# SMD_Breakout.net
KiCad netlist of a schematic drawn in EAGLE
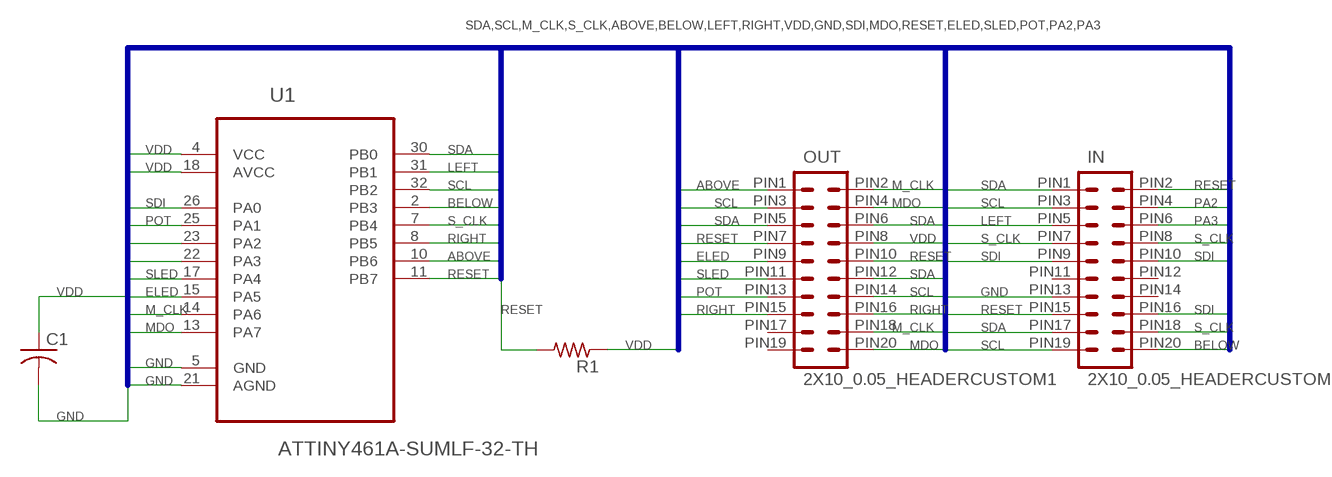
[diagram p0: schematic, sheet 1]

(export (version "E")
  (design (tool "Eeschema 10.0.6"))
  (components
    (comp (ref "C1")
      (value "C-USC0603")
      (footprint "eagle-import:C0603")
      (libsource (lib "eagle-import") (part "C-USC0603"))
    )
    (comp (ref "IN")
      (value "2X10_0.05_HEADERCUSTOM1")
      (footprint "eagle-import:2X10_CUSTOM")
      (libsource (lib "eagle-import") (part "2X10_0.05_HEADERCUSTOM1"))
    )
    (comp (ref "OUT")
      (value "2X10_0.05_HEADERCUSTOM1")
      (footprint "eagle-import:2X10_CUSTOM")
      (libsource (lib "eagle-import") (part "2X10_0.05_HEADERCUSTOM1"))
    )
    (comp (ref "R1")
      (value "R-US_R0603")
      (footprint "eagle-import:R0603")
      (libsource (lib "eagle-import") (part "R-US_R0603"))
    )
    (comp (ref "U1")
      (value "ATTINY461A-SUMLF-32-TH")
      (footprint "eagle-import:MLF32-TH")
      (libsource (lib "eagle-import") (part "ATTINY461A-SUMLF-32-TH"))
    )
  )
  (nets
    (net (code "1") (name "/ABOVE") (class "Default")
      (node (ref "OUT") (pin "PIN1") (pinfunction "1_PIN1") (pintype "passive"))
      (node (ref "U1") (pin "10") (pinfunction "PB6_10") (pintype "bidirectional"))
    )
    (net (code "2") (name "/BELOW") (class "Default")
      (node (ref "IN") (pin "PIN20") (pinfunction "20_PIN20") (pintype "passive"))
      (node (ref "U1") (pin "2") (pinfunction "PB3_2") (pintype "bidirectional"))
    )
    (net (code "3") (name "/ELED") (class "Default")
      (node (ref "OUT") (pin "PIN9") (pinfunction "9_PIN9") (pintype "passive"))
      (node (ref "U1") (pin "15") (pinfunction "PA5_15") (pintype "bidirectional"))
    )
    (net (code "4") (name "/GND") (class "Default")
      (node (ref "C1") (pin "2") (pinfunction "2_2") (pintype "passive"))
      (node (ref "IN") (pin "PIN13") (pinfunction "13_PIN13") (pintype "passive"))
      (node (ref "U1") (pin "21") (pinfunction "AGND_21") (pintype "passive"))
      (node (ref "U1") (pin "5") (pinfunction "GND_5") (pintype "passive"))
    )
    (net (code "5") (name "/LEFT") (class "Default")
      (node (ref "IN") (pin "PIN5") (pinfunction "5_PIN5") (pintype "passive"))
      (node (ref "U1") (pin "31") (pinfunction "PB1_31") (pintype "bidirectional"))
    )
    (net (code "6") (name "/MDO") (class "Default")
      (node (ref "OUT") (pin "PIN20") (pinfunction "20_PIN20") (pintype "passive"))
      (node (ref "OUT") (pin "PIN4") (pinfunction "4_PIN4") (pintype "passive"))
      (node (ref "U1") (pin "13") (pinfunction "PA7_13") (pintype "bidirectional"))
    )
    (net (code "7") (name "/M_CLK") (class "Default")
      (node (ref "OUT") (pin "PIN18") (pinfunction "18_PIN18") (pintype "passive"))
      (node (ref "OUT") (pin "PIN2") (pinfunction "2_PIN2") (pintype "passive"))
      (node (ref "U1") (pin "14") (pinfunction "PA6_14") (pintype "bidirectional"))
    )
    (net (code "8") (name "/PA2") (class "Default")
      (node (ref "IN") (pin "PIN4") (pinfunction "4_PIN4") (pintype "passive"))
      (node (ref "U1") (pin "23") (pinfunction "PA2_23") (pintype "bidirectional"))
    )
    (net (code "9") (name "/PA3") (class "Default")
      (node (ref "IN") (pin "PIN6") (pinfunction "6_PIN6") (pintype "passive"))
      (node (ref "U1") (pin "22") (pinfunction "PA3_22") (pintype "bidirectional"))
    )
    (net (code "10") (name "/POT") (class "Default")
      (node (ref "OUT") (pin "PIN13") (pinfunction "13_PIN13") (pintype "passive"))
      (node (ref "U1") (pin "25") (pinfunction "PA1_25") (pintype "bidirectional"))
    )
    (net (code "11") (name "/RESET") (class "Default")
      (node (ref "IN") (pin "PIN15") (pinfunction "15_PIN15") (pintype "passive"))
      (node (ref "IN") (pin "PIN2") (pinfunction "2_PIN2") (pintype "passive"))
      (node (ref "OUT") (pin "PIN10") (pinfunction "10_PIN10") (pintype "passive"))
      (node (ref "OUT") (pin "PIN7") (pinfunction "7_PIN7") (pintype "passive"))
      (node (ref "R1") (pin "2") (pinfunction "2_2") (pintype "passive"))
      (node (ref "U1") (pin "11") (pinfunction "PB7_11") (pintype "bidirectional"))
    )
    (net (code "12") (name "/RIGHT") (class "Default")
      (node (ref "OUT") (pin "PIN15") (pinfunction "15_PIN15") (pintype "passive"))
      (node (ref "OUT") (pin "PIN16") (pinfunction "16_PIN16") (pintype "passive"))
      (node (ref "U1") (pin "8") (pinfunction "PB5_8") (pintype "bidirectional"))
    )
    (net (code "13") (name "/SCL") (class "Default")
      (node (ref "IN") (pin "PIN19") (pinfunction "19_PIN19") (pintype "passive"))
      (node (ref "IN") (pin "PIN3") (pinfunction "3_PIN3") (pintype "passive"))
      (node (ref "OUT") (pin "PIN14") (pinfunction "14_PIN14") (pintype "passive"))
      (node (ref "OUT") (pin "PIN3") (pinfunction "3_PIN3") (pintype "passive"))
      (node (ref "U1") (pin "32") (pinfunction "PB2_32") (pintype "bidirectional"))
    )
    (net (code "14") (name "/SDA") (class "Default")
      (node (ref "IN") (pin "PIN1") (pinfunction "1_PIN1") (pintype "passive"))
      (node (ref "IN") (pin "PIN17") (pinfunction "17_PIN17") (pintype "passive"))
      (node (ref "OUT") (pin "PIN12") (pinfunction "12_PIN12") (pintype "passive"))
      (node (ref "OUT") (pin "PIN5") (pinfunction "5_PIN5") (pintype "passive"))
      (node (ref "OUT") (pin "PIN6") (pinfunction "6_PIN6") (pintype "passive"))
      (node (ref "U1") (pin "30") (pinfunction "PB0_30") (pintype "bidirectional"))
    )
    (net (code "15") (name "/SDI") (class "Default")
      (node (ref "IN") (pin "PIN10") (pinfunction "10_PIN10") (pintype "passive"))
      (node (ref "IN") (pin "PIN16") (pinfunction "16_PIN16") (pintype "passive"))
      (node (ref "IN") (pin "PIN9") (pinfunction "9_PIN9") (pintype "passive"))
      (node (ref "U1") (pin "26") (pinfunction "PA0_26") (pintype "bidirectional"))
    )
    (net (code "16") (name "/SLED") (class "Default")
      (node (ref "OUT") (pin "PIN11") (pinfunction "11_PIN11") (pintype "passive"))
      (node (ref "U1") (pin "17") (pinfunction "PA4_17") (pintype "bidirectional"))
    )
    (net (code "17") (name "/S_CLK") (class "Default")
      (node (ref "IN") (pin "PIN18") (pinfunction "18_PIN18") (pintype "passive"))
      (node (ref "IN") (pin "PIN7") (pinfunction "7_PIN7") (pintype "passive"))
      (node (ref "IN") (pin "PIN8") (pinfunction "8_PIN8") (pintype "passive"))
      (node (ref "U1") (pin "7") (pinfunction "PB4_7") (pintype "bidirectional"))
    )
    (net (code "18") (name "/VDD") (class "Default")
      (node (ref "C1") (pin "1") (pinfunction "1_1") (pintype "passive"))
      (node (ref "OUT") (pin "PIN8") (pinfunction "8_PIN8") (pintype "passive"))
      (node (ref "R1") (pin "1") (pinfunction "1_1") (pintype "passive"))
      (node (ref "U1") (pin "18") (pinfunction "AVCC_18") (pintype "power_in"))
      (node (ref "U1") (pin "4") (pinfunction "VCC_4") (pintype "power_in"))
    )
    (net (code "20") (name "unconnected-(IN-11-PadPIN11)") (class "Default")
      (node (ref "IN") (pin "PIN11") (pinfunction "11_PIN11") (pintype "passive"))
    )
    (net (code "21") (name "unconnected-(IN-12-PadPIN12)") (class "Default")
      (node (ref "IN") (pin "PIN12") (pinfunction "12_PIN12") (pintype "passive"))
    )
    (net (code "22") (name "unconnected-(IN-14-PadPIN14)") (class "Default")
      (node (ref "IN") (pin "PIN14") (pinfunction "14_PIN14") (pintype "passive"))
    )
    (net (code "23") (name "unconnected-(OUT-17-PadPIN17)") (class "Default")
      (node (ref "OUT") (pin "PIN17") (pinfunction "17_PIN17") (pintype "passive"))
    )
    (net (code "24") (name "unconnected-(OUT-19-PadPIN19)") (class "Default")
      (node (ref "OUT") (pin "PIN19") (pinfunction "19_PIN19") (pintype "passive"))
    )
  )
)
